# Keyboard.net
KiCad netlist of a schematic drawn in Altium Designer
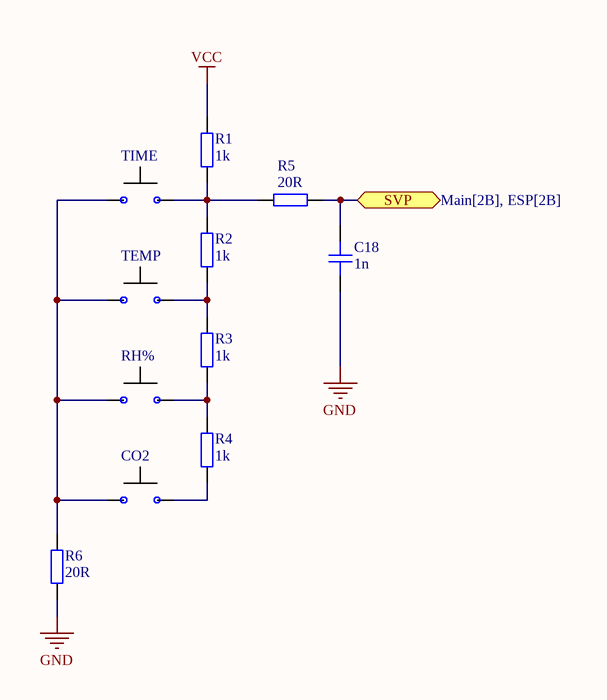
[diagram p0: Keyboard.SchDoc]

(export (version "E")
  (design (tool "Eeschema 10.0.6"))
  (components
    (comp (ref "C18")
      (value "1n")
      (footprint "CAP_0805")
      (description "Capacitor SMD 0805")
      (libsource (lib "Schematic-Lib-PhilsLab") (part "CAP_0805"))
    )
    (comp (ref "CO2")
      (value "Tact_Switch")
      (footprint "Tact_Switch")
      (libsource (lib "Schematic_Library_TM") (part "Tact_Switch"))
    )
    (comp (ref "R1")
      (value "1k")
      (footprint "RES_0805")
      (description "Resistor SMD 0805")
      (libsource (lib "Schematic-Lib-PhilsLab") (part "RES_0805"))
    )
    (comp (ref "R2")
      (value "1k")
      (footprint "RES_0805")
      (description "Resistor SMD 0805")
      (libsource (lib "Schematic-Lib-PhilsLab") (part "RES_0805"))
    )
    (comp (ref "R3")
      (value "1k")
      (footprint "RES_0805")
      (description "Resistor SMD 0805")
      (libsource (lib "Schematic-Lib-PhilsLab") (part "RES_0805"))
    )
    (comp (ref "R4")
      (value "1k")
      (footprint "RES_0805")
      (description "Resistor SMD 0805")
      (libsource (lib "Schematic-Lib-PhilsLab") (part "RES_0805"))
    )
    (comp (ref "R5")
      (value "20R")
      (footprint "RES_0805")
      (description "Resistor SMD 0805")
      (libsource (lib "Schematic-Lib-PhilsLab") (part "RES_0805"))
    )
    (comp (ref "R6")
      (value "20R")
      (footprint "RES_0805")
      (description "Resistor SMD 0805")
      (libsource (lib "Schematic-Lib-PhilsLab") (part "RES_0805"))
    )
    (comp (ref "RH%")
      (value "Tact_Switch")
      (footprint "Tact_Switch")
      (libsource (lib "Schematic_Library_TM") (part "Tact_Switch"))
    )
    (comp (ref "TEMP")
      (value "Tact_Switch")
      (footprint "Tact_Switch")
      (libsource (lib "Schematic_Library_TM") (part "Tact_Switch"))
    )
    (comp (ref "TIME")
      (value "Tact_Switch")
      (footprint "Tact_Switch")
      (libsource (lib "Schematic_Library_TM") (part "Tact_Switch"))
    )
  )
  (nets
    (net (code "1") (name "/SVP") (class "Default")
      (node (ref "C18") (pin "2") (pinfunction "2_2") (pintype "passive"))
      (node (ref "R5") (pin "1") (pinfunction "1_1") (pintype "passive"))
    )
    (net (code "2") (name "GND") (class "Default")
      (node (ref "C18") (pin "1") (pinfunction "1_1") (pintype "passive"))
      (node (ref "R6") (pin "1") (pinfunction "1_1") (pintype "passive"))
    )
    (net (code "3") (name "Net-(CO2-PIN-Pad1)") (class "Default")
      (node (ref "CO2") (pin "1") (pinfunction "PIN_1") (pintype "passive"))
      (node (ref "R6") (pin "2") (pinfunction "2_2") (pintype "passive"))
      (node (ref "RH%") (pin "1") (pinfunction "PIN_1") (pintype "passive"))
      (node (ref "TEMP") (pin "1") (pinfunction "PIN_1") (pintype "passive"))
      (node (ref "TIME") (pin "1") (pinfunction "PIN_1") (pintype "passive"))
    )
    (net (code "4") (name "Net-(CO2-PIN-Pad2)") (class "Default")
      (node (ref "CO2") (pin "2") (pinfunction "PIN_2") (pintype "passive"))
      (node (ref "R4") (pin "1") (pinfunction "1_1") (pintype "passive"))
    )
    (net (code "5") (name "Net-(R1-Pad1)") (class "Default")
      (node (ref "R1") (pin "1") (pinfunction "1_1") (pintype "passive"))
      (node (ref "R2") (pin "2") (pinfunction "2_2") (pintype "passive"))
      (node (ref "R5") (pin "2") (pinfunction "2_2") (pintype "passive"))
      (node (ref "TIME") (pin "2") (pinfunction "PIN_2") (pintype "passive"))
    )
    (net (code "6") (name "Net-(R2-Pad1)") (class "Default")
      (node (ref "R2") (pin "1") (pinfunction "1_1") (pintype "passive"))
      (node (ref "R3") (pin "2") (pinfunction "2_2") (pintype "passive"))
      (node (ref "TEMP") (pin "2") (pinfunction "PIN_2") (pintype "passive"))
    )
    (net (code "7") (name "Net-(R3-Pad1)") (class "Default")
      (node (ref "R3") (pin "1") (pinfunction "1_1") (pintype "passive"))
      (node (ref "R4") (pin "2") (pinfunction "2_2") (pintype "passive"))
      (node (ref "RH%") (pin "2") (pinfunction "PIN_2") (pintype "passive"))
    )
    (net (code "8") (name "VCC") (class "Default")
      (node (ref "R1") (pin "2") (pinfunction "2_2") (pintype "passive"))
    )
  )
)
